# Level_shifter.net
KiCad netlist of a schematic drawn in Altium Designer
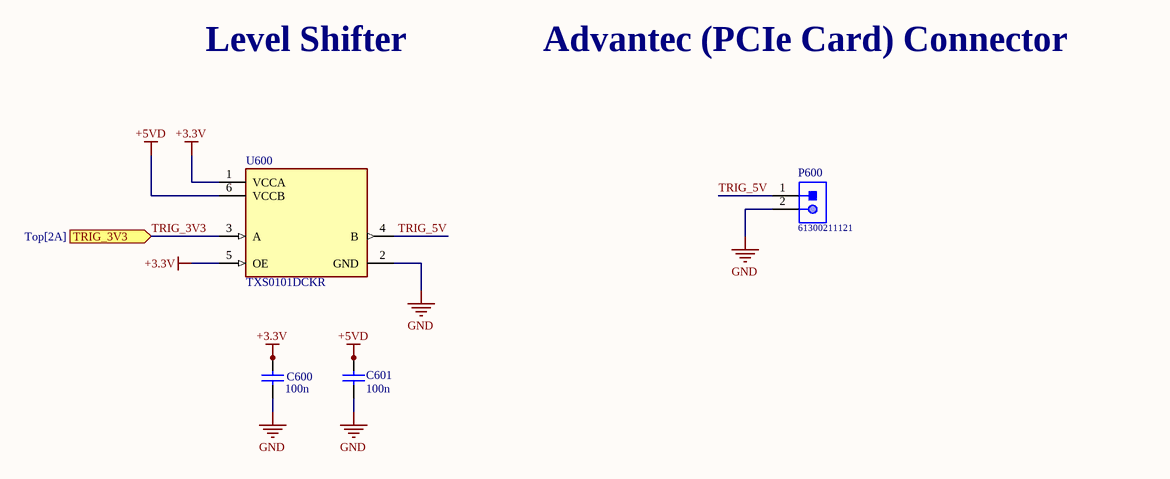
[diagram p0: Level_shifter.SchDoc]

(export (version "E")
  (design (tool "Eeschema 10.0.6"))
  (components
    (comp (ref "C600")
      (value "100n")
      (footprint "SAMS-C0603-2_M")
      (description "Multi-layer Ceramic Capacitor, -55 to 125 degC, 2-Pin SMD (0603), RoHS, Tape and Reel")
      (fields (field (name "MANUFACTURER") "Samsung Electro-Mechanics"))
      (libsource (lib "Altium Content Vault") (part "CAP-NP-2"))
    )
    (comp (ref "C601")
      (value "100n")
      (footprint "SAMS-C0603-2_M")
      (description "Multi-layer Ceramic Capacitor, -55 to 125 degC, 2-Pin SMD (0603), RoHS, Tape and Reel")
      (fields (field (name "MANUFACTURER") "Samsung Electro-Mechanics"))
      (libsource (lib "Altium Content Vault") (part "CAP-NP-2"))
    )
    (comp (ref "P600")
      (value "61300211121")
      (footprint "61300211121")
      (description "THT Vertical Pin Header WR-PHD, Pitch 2.54 mm, Single Row, 2 pins")
      (fields (field (name "MANUFACTURER") "Wurth Elektronik") (field (name "PUBLISHER") "WurthElektronik"))
      (libsource (lib "Altium Content Vault") (part "WE-CN-1P-M-R2"))
    )
    (comp (ref "U600")
      (value "TXS0101DCKR")
      (footprint "FP-DCK0006A-MFG")
      (description "IC TRNSLTR BIDIRECTIONAL SC70-6")
      (libsource (lib "Altium Content Vault") (part "18d0a579b707e31b994b2d2e44b5946"))
    )
  )
  (nets
    (net (code "1") (name "+3.3V") (class "Default")
      (node (ref "C600") (pin "2") (pinfunction "2_2") (pintype "passive"))
      (node (ref "U600") (pin "1") (pinfunction "VCCA_1") (pintype "power_in"))
      (node (ref "U600") (pin "5") (pinfunction "OE_5") (pintype "input"))
    )
    (net (code "2") (name "+5VD") (class "Default")
      (node (ref "C601") (pin "2") (pinfunction "2_2") (pintype "passive"))
      (node (ref "U600") (pin "6") (pinfunction "VCCB_6") (pintype "power_in"))
    )
    (net (code "3") (name "/TRIG_3V3") (class "Default")
      (node (ref "U600") (pin "3") (pinfunction "A_3") (pintype "input"))
    )
    (net (code "4") (name "/TRIG_5V") (class "Default")
      (node (ref "P600") (pin "1") (pinfunction "1_1") (pintype "passive"))
      (node (ref "U600") (pin "4") (pinfunction "B_4") (pintype "output"))
    )
    (net (code "5") (name "GND") (class "Default")
      (node (ref "C600") (pin "1") (pinfunction "1_1") (pintype "passive"))
      (node (ref "C601") (pin "1") (pinfunction "1_1") (pintype "passive"))
      (node (ref "P600") (pin "2") (pinfunction "2_2") (pintype "passive"))
      (node (ref "U600") (pin "2") (pinfunction "GND_2") (pintype "power_in"))
    )
  )
)
